# transistor-h-bridge.net
KiCad netlist of a schematic drawn in EAGLE
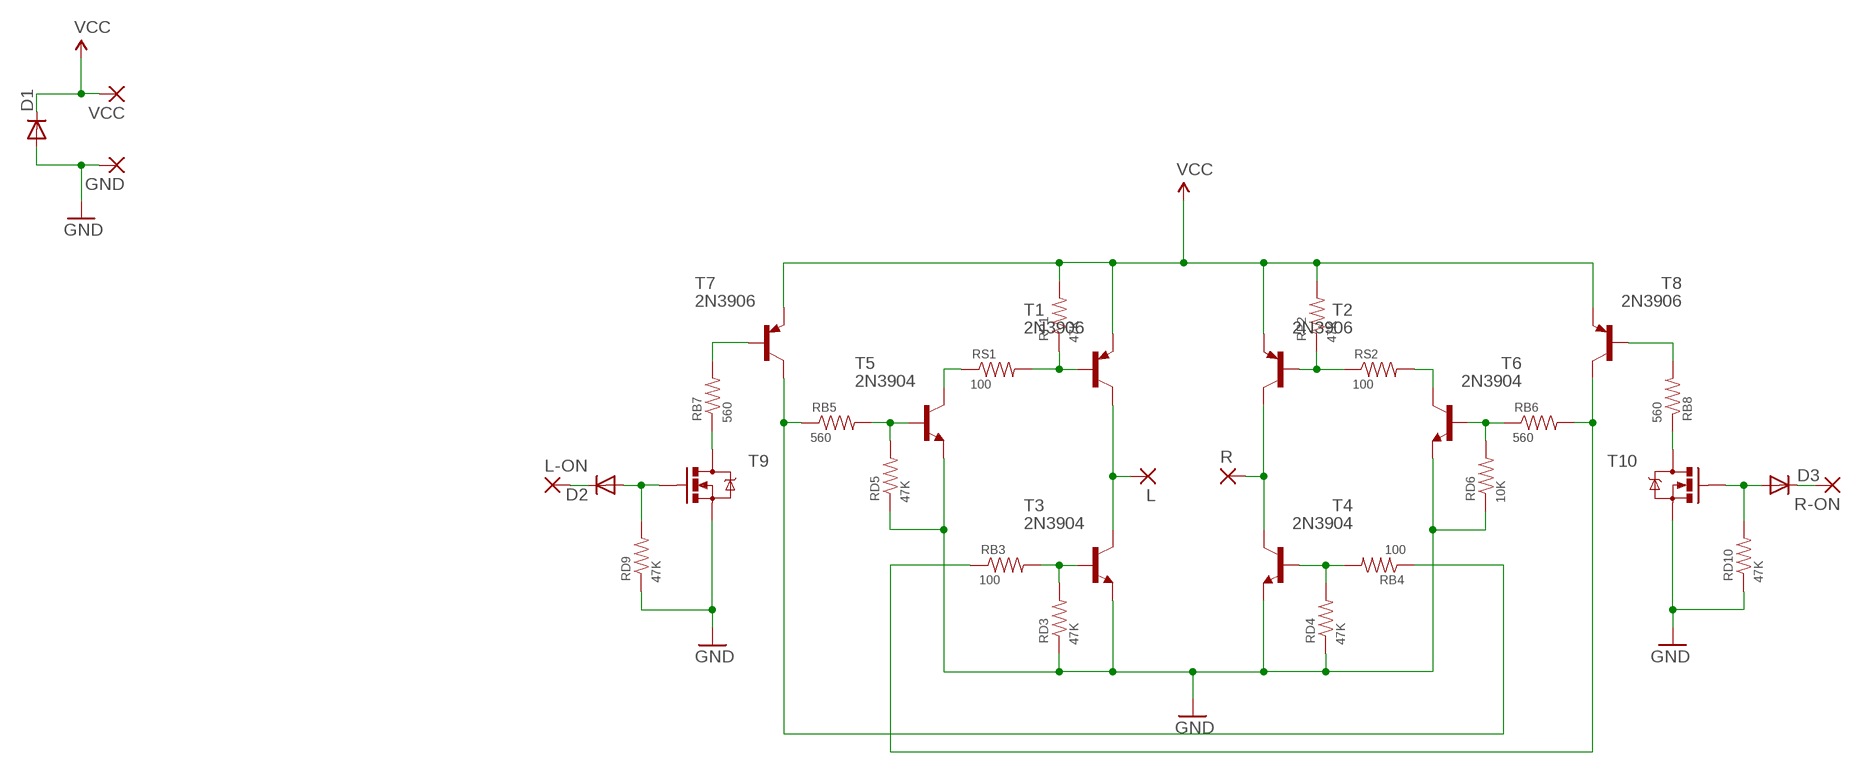
[diagram p0: schematic, sheet 1]

(export (version "E")
  (design (tool "Eeschema 10.0.6"))
  (components
    (comp (ref "D1")
      (value "DIODE1N4148")
      (footprint "eagle-import:DIODE-1N4148")
      (libsource (lib "eagle-import") (part "DIODE1N4148"))
    )
    (comp (ref "D2")
      (value "DIODE1N4148")
      (footprint "eagle-import:DIODE-1N4148")
      (libsource (lib "eagle-import") (part "DIODE1N4148"))
    )
    (comp (ref "D3")
      (value "DIODE1N4148")
      (footprint "eagle-import:DIODE-1N4148")
      (libsource (lib "eagle-import") (part "DIODE1N4148"))
    )
    (comp (ref "GND")
      (value "WIREPAD2,54/0,8")
      (footprint "eagle-import:2,54_0,8")
      (libsource (lib "eagle-import") (part "WIREPAD2,54/0,8"))
    )
    (comp (ref "L")
      (value "WIREPAD2,54/0,8")
      (footprint "eagle-import:2,54_0,8")
      (libsource (lib "eagle-import") (part "WIREPAD2,54/0,8"))
    )
    (comp (ref "L-ON")
      (value "WIREPAD2,54/0,8")
      (footprint "eagle-import:2,54_0,8")
      (libsource (lib "eagle-import") (part "WIREPAD2,54/0,8"))
    )
    (comp (ref "R")
      (value "WIREPAD2,54/0,8")
      (footprint "eagle-import:2,54_0,8")
      (libsource (lib "eagle-import") (part "WIREPAD2,54/0,8"))
    )
    (comp (ref "R-ON")
      (value "WIREPAD2,54/0,8")
      (footprint "eagle-import:2,54_0,8")
      (libsource (lib "eagle-import") (part "WIREPAD2,54/0,8"))
    )
    (comp (ref "RB3")
      (value "100")
      (footprint "eagle-import:VERT-PTH")
      (libsource (lib "eagle-import") (part "RESISTOR-PTH"))
    )
    (comp (ref "RB4")
      (value "100")
      (footprint "eagle-import:VERT-PTH")
      (libsource (lib "eagle-import") (part "RESISTOR-PTH"))
    )
    (comp (ref "RB5")
      (value "560")
      (footprint "eagle-import:VERT-PTH")
      (libsource (lib "eagle-import") (part "RESISTOR-PTH"))
    )
    (comp (ref "RB6")
      (value "560")
      (footprint "eagle-import:VERT-PTH")
      (libsource (lib "eagle-import") (part "RESISTOR-PTH"))
    )
    (comp (ref "RB7")
      (value "560")
      (footprint "eagle-import:VERT-PTH")
      (libsource (lib "eagle-import") (part "RESISTOR-PTH"))
    )
    (comp (ref "RB8")
      (value "560")
      (footprint "eagle-import:VERT-PTH")
      (libsource (lib "eagle-import") (part "RESISTOR-PTH"))
    )
    (comp (ref "RD3")
      (value "47K")
      (footprint "eagle-import:VERT-PTH")
      (libsource (lib "eagle-import") (part "RESISTOR-PTH"))
    )
    (comp (ref "RD4")
      (value "47K")
      (footprint "eagle-import:VERT-PTH")
      (libsource (lib "eagle-import") (part "RESISTOR-PTH"))
    )
    (comp (ref "RD5")
      (value "47K")
      (footprint "eagle-import:VERT-PTH")
      (libsource (lib "eagle-import") (part "RESISTOR-PTH"))
    )
    (comp (ref "RD6")
      (value "10K")
      (footprint "eagle-import:VERT-PTH")
      (libsource (lib "eagle-import") (part "RESISTOR-PTH"))
    )
    (comp (ref "RD9")
      (value "47K")
      (footprint "eagle-import:VERT-PTH")
      (libsource (lib "eagle-import") (part "RESISTOR-PTH"))
    )
    (comp (ref "RD10")
      (value "47K")
      (footprint "eagle-import:VERT-PTH")
      (libsource (lib "eagle-import") (part "RESISTOR-PTH"))
    )
    (comp (ref "RP1")
      (value "47K")
      (footprint "eagle-import:VERT-PTH")
      (libsource (lib "eagle-import") (part "RESISTOR-PTH"))
    )
    (comp (ref "RP2")
      (value "47K")
      (footprint "eagle-import:VERT-PTH")
      (libsource (lib "eagle-import") (part "RESISTOR-PTH"))
    )
    (comp (ref "RS1")
      (value "100")
      (footprint "eagle-import:VERT-PTH")
      (libsource (lib "eagle-import") (part "RESISTOR-PTH"))
    )
    (comp (ref "RS2")
      (value "100")
      (footprint "eagle-import:VERT-PTH")
      (libsource (lib "eagle-import") (part "RESISTOR-PTH"))
    )
    (comp (ref "T1")
      (value "2N3906")
      (footprint "eagle-import:TO92")
      (libsource (lib "eagle-import") (part "2N3906"))
    )
    (comp (ref "T2")
      (value "2N3906")
      (footprint "eagle-import:TO92")
      (libsource (lib "eagle-import") (part "2N3906"))
    )
    (comp (ref "T3")
      (value "2N3904")
      (footprint "eagle-import:TO92")
      (libsource (lib "eagle-import") (part "2N3904"))
    )
    (comp (ref "T4")
      (value "2N3904")
      (footprint "eagle-import:TO92")
      (libsource (lib "eagle-import") (part "2N3904"))
    )
    (comp (ref "T5")
      (value "2N3904")
      (footprint "eagle-import:TO92")
      (libsource (lib "eagle-import") (part "2N3904"))
    )
    (comp (ref "T6")
      (value "2N3904")
      (footprint "eagle-import:TO92")
      (libsource (lib "eagle-import") (part "2N3904"))
    )
    (comp (ref "T7")
      (value "2N3906")
      (footprint "eagle-import:TO92")
      (libsource (lib "eagle-import") (part "2N3906"))
    )
    (comp (ref "T8")
      (value "2N3906")
      (footprint "eagle-import:TO92")
      (libsource (lib "eagle-import") (part "2N3906"))
    )
    (comp (ref "T9")
      (value "MOSFET-NCHANNELPTH")
      (footprint "eagle-import:TO-92")
      (libsource (lib "eagle-import") (part "MOSFET-NCHANNELPTH"))
    )
    (comp (ref "T10")
      (value "MOSFET-NCHANNELPTH")
      (footprint "eagle-import:TO-92")
      (libsource (lib "eagle-import") (part "MOSFET-NCHANNELPTH"))
    )
    (comp (ref "VCC")
      (value "WIREPAD2,54/0,8")
      (footprint "eagle-import:2,54_0,8")
      (libsource (lib "eagle-import") (part "WIREPAD2,54/0,8"))
    )
  )
  (nets
    (net (code "1") (name "GND") (class "Default")
      (node (ref "D1") (pin "A") (pinfunction "A_A") (pintype "passive"))
      (node (ref "GND") (pin "1") (pinfunction "P_1") (pintype "passive"))
      (node (ref "RD10") (pin "1") (pinfunction "G$1_1") (pintype "bidirectional"))
      (node (ref "RD3") (pin "1") (pinfunction "G$1_1") (pintype "bidirectional"))
      (node (ref "RD4") (pin "1") (pinfunction "G$1_1") (pintype "bidirectional"))
      (node (ref "RD5") (pin "1") (pinfunction "G$1_1") (pintype "bidirectional"))
      (node (ref "RD6") (pin "1") (pinfunction "G$1_1") (pintype "bidirectional"))
      (node (ref "RD9") (pin "1") (pinfunction "G$1_1") (pintype "bidirectional"))
      (node (ref "T10") (pin "2") (pinfunction "S_2") (pintype "passive"))
      (node (ref "T3") (pin "3") (pinfunction "E_3") (pintype "passive"))
      (node (ref "T4") (pin "3") (pinfunction "E_3") (pintype "passive"))
      (node (ref "T5") (pin "3") (pinfunction "E_3") (pintype "passive"))
      (node (ref "T6") (pin "3") (pinfunction "E_3") (pintype "passive"))
      (node (ref "T9") (pin "2") (pinfunction "S_2") (pintype "passive"))
    )
    (net (code "2") (name "Net-(L-ON-P)") (class "Default")
      (node (ref "D2") (pin "C") (pinfunction "C_C") (pintype "passive"))
      (node (ref "L-ON") (pin "1") (pinfunction "P_1") (pintype "passive"))
    )
    (net (code "3") (name "Net-(L-P)") (class "Default")
      (node (ref "L") (pin "1") (pinfunction "P_1") (pintype "passive"))
      (node (ref "T1") (pin "1") (pinfunction "C_1") (pintype "passive"))
      (node (ref "T3") (pin "1") (pinfunction "C_1") (pintype "passive"))
    )
    (net (code "4") (name "Net-(R-ON-P)") (class "Default")
      (node (ref "D3") (pin "C") (pinfunction "C_C") (pintype "passive"))
      (node (ref "R-ON") (pin "1") (pinfunction "P_1") (pintype "passive"))
    )
    (net (code "5") (name "Net-(R-P)") (class "Default")
      (node (ref "R") (pin "1") (pinfunction "P_1") (pintype "passive"))
      (node (ref "T2") (pin "1") (pinfunction "C_1") (pintype "passive"))
      (node (ref "T4") (pin "1") (pinfunction "C_1") (pintype "passive"))
    )
    (net (code "6") (name "Net-(RB3-G$1)") (class "Default")
      (node (ref "RB3") (pin "1") (pinfunction "G$1_1") (pintype "bidirectional"))
      (node (ref "RB6") (pin "2") (pinfunction "G$2_2") (pintype "bidirectional"))
      (node (ref "T8") (pin "1") (pinfunction "C_1") (pintype "passive"))
    )
    (net (code "7") (name "Net-(RB3-G$2)") (class "Default")
      (node (ref "RB3") (pin "2") (pinfunction "G$2_2") (pintype "bidirectional"))
      (node (ref "RD3") (pin "2") (pinfunction "G$2_2") (pintype "bidirectional"))
      (node (ref "T3") (pin "2") (pinfunction "B_2") (pintype "passive"))
    )
    (net (code "8") (name "Net-(RB4-G$1)") (class "Default")
      (node (ref "RB4") (pin "1") (pinfunction "G$1_1") (pintype "bidirectional"))
      (node (ref "RB5") (pin "1") (pinfunction "G$1_1") (pintype "bidirectional"))
      (node (ref "T7") (pin "1") (pinfunction "C_1") (pintype "passive"))
    )
    (net (code "9") (name "Net-(RB4-G$2)") (class "Default")
      (node (ref "RB4") (pin "2") (pinfunction "G$2_2") (pintype "bidirectional"))
      (node (ref "RD4") (pin "2") (pinfunction "G$2_2") (pintype "bidirectional"))
      (node (ref "T4") (pin "2") (pinfunction "B_2") (pintype "passive"))
    )
    (net (code "10") (name "Net-(RB5-G$2)") (class "Default")
      (node (ref "RB5") (pin "2") (pinfunction "G$2_2") (pintype "bidirectional"))
      (node (ref "RD5") (pin "2") (pinfunction "G$2_2") (pintype "bidirectional"))
      (node (ref "T5") (pin "2") (pinfunction "B_2") (pintype "passive"))
    )
    (net (code "11") (name "Net-(RB6-G$1)") (class "Default")
      (node (ref "RB6") (pin "1") (pinfunction "G$1_1") (pintype "bidirectional"))
      (node (ref "RD6") (pin "2") (pinfunction "G$2_2") (pintype "bidirectional"))
      (node (ref "T6") (pin "2") (pinfunction "B_2") (pintype "passive"))
    )
    (net (code "12") (name "Net-(RB7-G$1)") (class "Default")
      (node (ref "RB7") (pin "1") (pinfunction "G$1_1") (pintype "bidirectional"))
      (node (ref "T9") (pin "1") (pinfunction "D_1") (pintype "passive"))
    )
    (net (code "13") (name "Net-(RB7-G$2)") (class "Default")
      (node (ref "RB7") (pin "2") (pinfunction "G$2_2") (pintype "bidirectional"))
      (node (ref "T7") (pin "2") (pinfunction "B_2") (pintype "passive"))
    )
    (net (code "14") (name "Net-(RB8-G$1)") (class "Default")
      (node (ref "RB8") (pin "1") (pinfunction "G$1_1") (pintype "bidirectional"))
      (node (ref "T10") (pin "1") (pinfunction "D_1") (pintype "passive"))
    )
    (net (code "15") (name "Net-(RB8-G$2)") (class "Default")
      (node (ref "RB8") (pin "2") (pinfunction "G$2_2") (pintype "bidirectional"))
      (node (ref "T8") (pin "2") (pinfunction "B_2") (pintype "passive"))
    )
    (net (code "16") (name "Net-(RD9-G$2)") (class "Default")
      (node (ref "D2") (pin "A") (pinfunction "A_A") (pintype "passive"))
      (node (ref "RD9") (pin "2") (pinfunction "G$2_2") (pintype "bidirectional"))
      (node (ref "T9") (pin "3") (pinfunction "G_3") (pintype "passive"))
    )
    (net (code "17") (name "Net-(RD10-G$2)") (class "Default")
      (node (ref "D3") (pin "A") (pinfunction "A_A") (pintype "passive"))
      (node (ref "RD10") (pin "2") (pinfunction "G$2_2") (pintype "bidirectional"))
      (node (ref "T10") (pin "3") (pinfunction "G_3") (pintype "passive"))
    )
    (net (code "18") (name "Net-(RP1-G$1)") (class "Default")
      (node (ref "RP1") (pin "1") (pinfunction "G$1_1") (pintype "bidirectional"))
      (node (ref "RS1") (pin "2") (pinfunction "G$2_2") (pintype "bidirectional"))
      (node (ref "T1") (pin "2") (pinfunction "B_2") (pintype "passive"))
    )
    (net (code "19") (name "Net-(RP2-G$1)") (class "Default")
      (node (ref "RP2") (pin "1") (pinfunction "G$1_1") (pintype "bidirectional"))
      (node (ref "RS2") (pin "1") (pinfunction "G$1_1") (pintype "bidirectional"))
      (node (ref "T2") (pin "2") (pinfunction "B_2") (pintype "passive"))
    )
    (net (code "20") (name "Net-(RS1-G$1)") (class "Default")
      (node (ref "RS1") (pin "1") (pinfunction "G$1_1") (pintype "bidirectional"))
      (node (ref "T5") (pin "1") (pinfunction "C_1") (pintype "passive"))
    )
    (net (code "21") (name "Net-(RS2-G$2)") (class "Default")
      (node (ref "RS2") (pin "2") (pinfunction "G$2_2") (pintype "bidirectional"))
      (node (ref "T6") (pin "1") (pinfunction "C_1") (pintype "passive"))
    )
    (net (code "22") (name "VCC") (class "Default")
      (node (ref "D1") (pin "C") (pinfunction "C_C") (pintype "passive"))
      (node (ref "RP1") (pin "2") (pinfunction "G$2_2") (pintype "bidirectional"))
      (node (ref "RP2") (pin "2") (pinfunction "G$2_2") (pintype "bidirectional"))
      (node (ref "T1") (pin "3") (pinfunction "E_3") (pintype "passive"))
      (node (ref "T2") (pin "3") (pinfunction "E_3") (pintype "passive"))
      (node (ref "T7") (pin "3") (pinfunction "E_3") (pintype "passive"))
      (node (ref "T8") (pin "3") (pinfunction "E_3") (pintype "passive"))
      (node (ref "VCC") (pin "1") (pinfunction "P_1") (pintype "passive"))
    )
  )
)
